# F20_NoMCU_PDM_V1.net
KiCad netlist of a schematic drawn in EAGLE
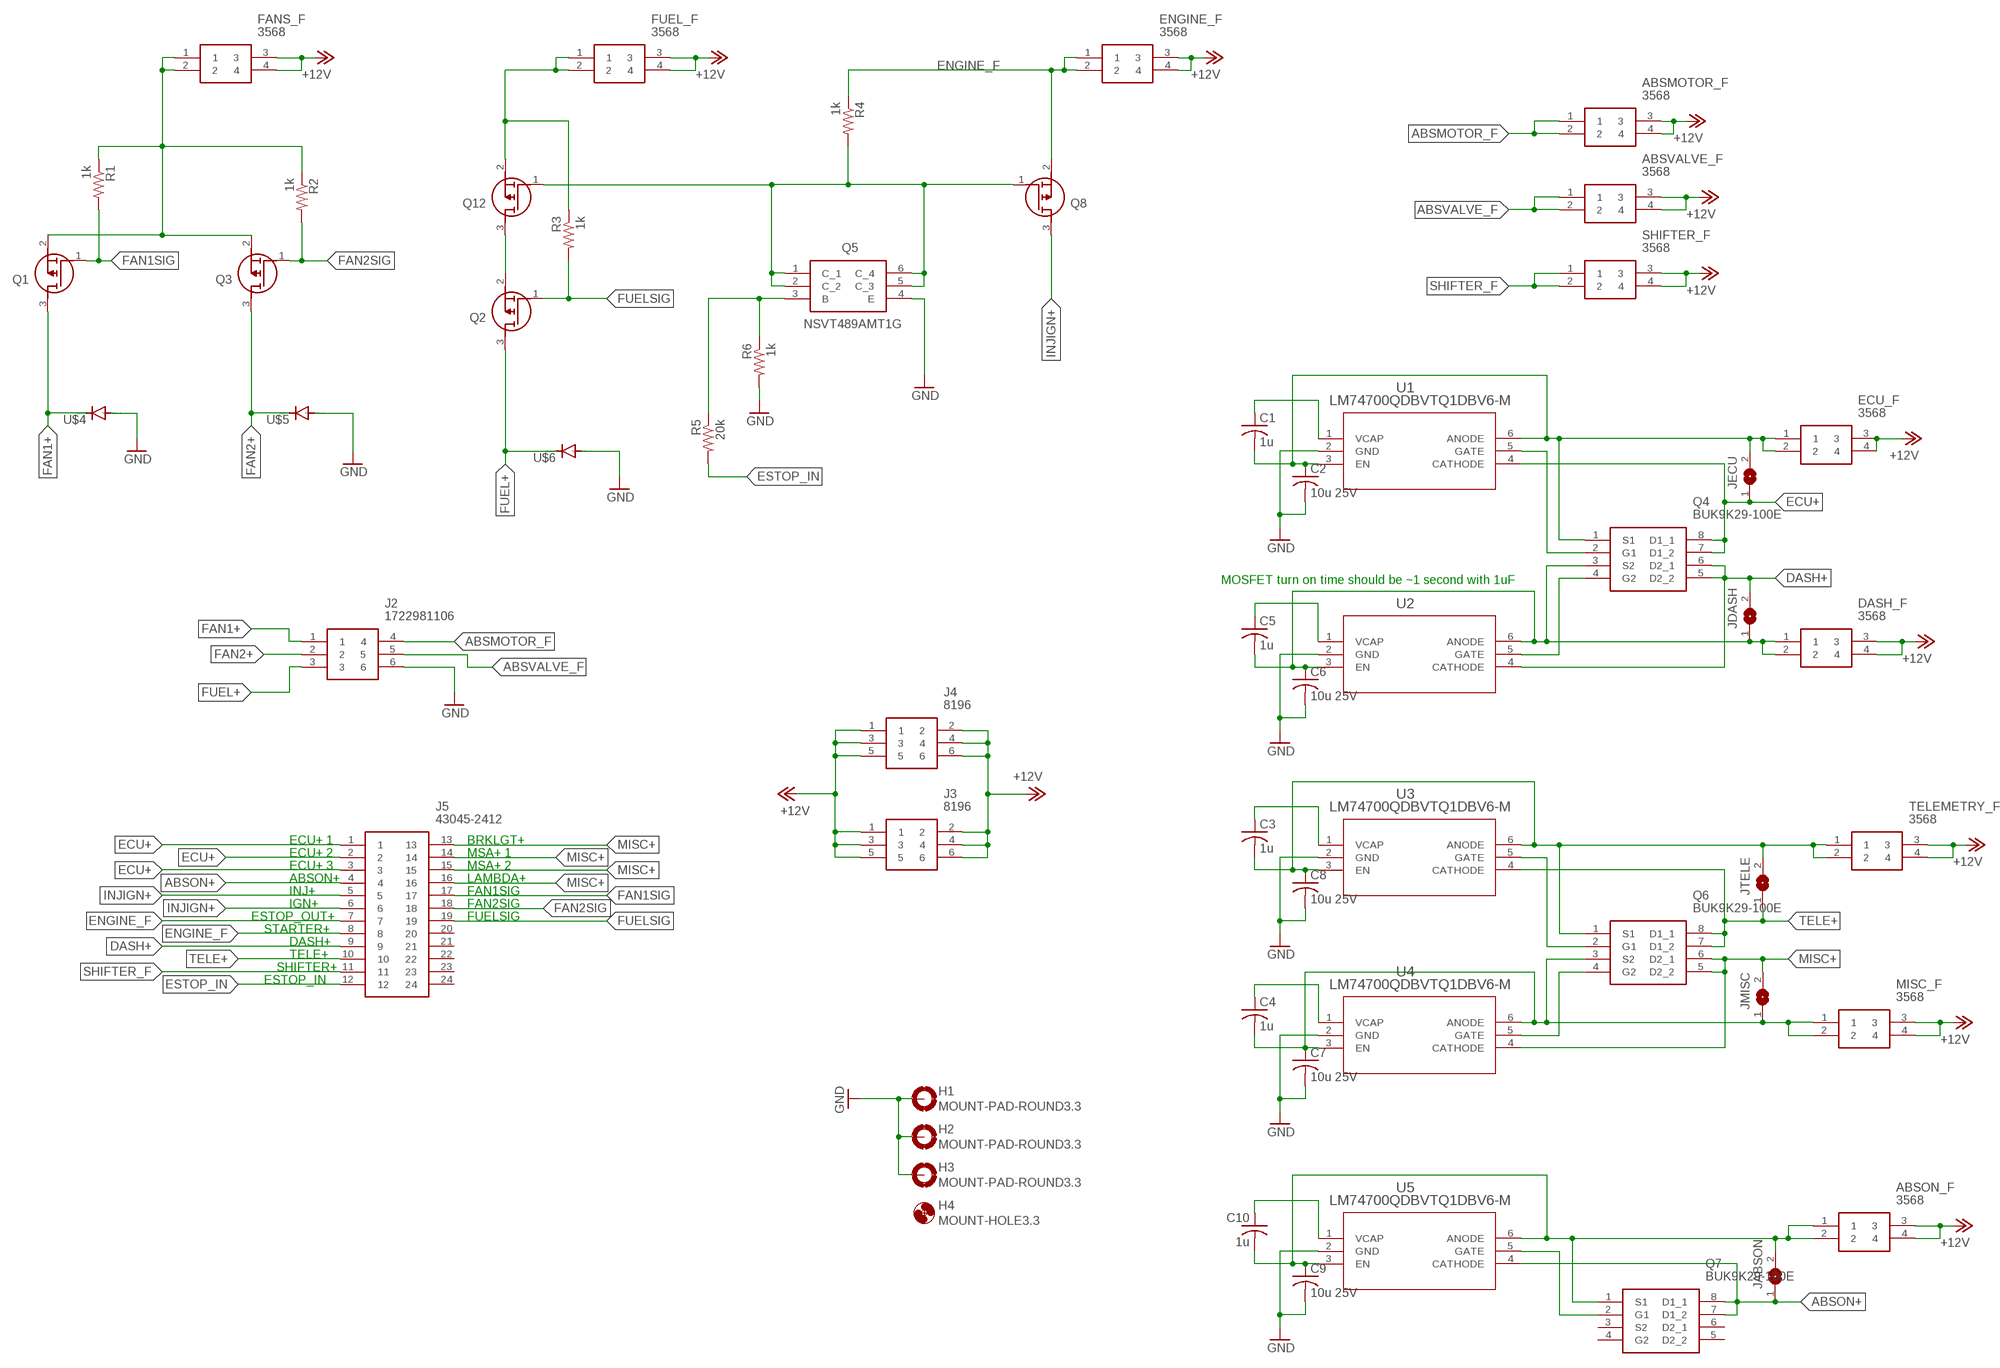
[diagram p0: schematic, sheet 1]

(export (version "E")
  (design (tool "Eeschema 10.0.6"))
  (components
    (comp (ref "ABSMOTOR_F")
      (value "3568")
      (footprint "eagle-import:3568")
      (fields (field (name "MOUSER_PART_NUMBER") "534-3568"))
      (libsource (lib "eagle-import") (part "3568"))
    )
    (comp (ref "ABSON_F")
      (value "3568")
      (footprint "eagle-import:3568")
      (fields (field (name "MOUSER_PART_NUMBER") "534-3568"))
      (libsource (lib "eagle-import") (part "3568"))
    )
    (comp (ref "ABSVALVE_F")
      (value "3568")
      (footprint "eagle-import:3568")
      (fields (field (name "MOUSER_PART_NUMBER") "534-3568"))
      (libsource (lib "eagle-import") (part "3568"))
    )
    (comp (ref "C1")
      (value "1u")
      (footprint "eagle-import:C0805")
      (libsource (lib "eagle-import") (part "C-USC0805"))
    )
    (comp (ref "C2")
      (value "10u 25V")
      (footprint "eagle-import:C0805")
      (libsource (lib "eagle-import") (part "C-USC0805"))
    )
    (comp (ref "C3")
      (value "1u")
      (footprint "eagle-import:C0805")
      (libsource (lib "eagle-import") (part "C-USC0805"))
    )
    (comp (ref "C4")
      (value "1u")
      (footprint "eagle-import:C0805")
      (libsource (lib "eagle-import") (part "C-USC0805"))
    )
    (comp (ref "C5")
      (value "1u")
      (footprint "eagle-import:C0805")
      (libsource (lib "eagle-import") (part "C-USC0805"))
    )
    (comp (ref "C6")
      (value "10u 25V")
      (footprint "eagle-import:C0805")
      (libsource (lib "eagle-import") (part "C-USC0805"))
    )
    (comp (ref "C7")
      (value "10u 25V")
      (footprint "eagle-import:C0805")
      (libsource (lib "eagle-import") (part "C-USC0805"))
    )
    (comp (ref "C8")
      (value "10u 25V")
      (footprint "eagle-import:C0805")
      (libsource (lib "eagle-import") (part "C-USC0805"))
    )
    (comp (ref "C9")
      (value "10u 25V")
      (footprint "eagle-import:C0805")
      (libsource (lib "eagle-import") (part "C-USC0805"))
    )
    (comp (ref "C10")
      (value "1u")
      (footprint "eagle-import:C0805")
      (libsource (lib "eagle-import") (part "C-USC0805"))
    )
    (comp (ref "DASH_F")
      (value "3568")
      (footprint "eagle-import:3568")
      (fields (field (name "MOUSER_PART_NUMBER") "534-3568"))
      (libsource (lib "eagle-import") (part "3568"))
    )
    (comp (ref "ECU_F")
      (value "3568")
      (footprint "eagle-import:3568")
      (fields (field (name "MOUSER_PART_NUMBER") "534-3568"))
      (libsource (lib "eagle-import") (part "3568"))
    )
    (comp (ref "ENGINE_F")
      (value "3568")
      (footprint "eagle-import:3568")
      (fields (field (name "MOUSER_PART_NUMBER") "534-3568"))
      (libsource (lib "eagle-import") (part "3568"))
    )
    (comp (ref "FANS_F")
      (value "3568")
      (footprint "eagle-import:3568")
      (fields (field (name "MOUSER_PART_NUMBER") "534-3568"))
      (libsource (lib "eagle-import") (part "3568"))
    )
    (comp (ref "FUEL_F")
      (value "3568")
      (footprint "eagle-import:3568")
      (fields (field (name "MOUSER_PART_NUMBER") "534-3568"))
      (libsource (lib "eagle-import") (part "3568"))
    )
    (comp (ref "H1")
      (value "MOUNT-PAD-ROUND3.3")
      (footprint "eagle-import:3,3-PAD")
      (libsource (lib "eagle-import") (part "MOUNT-PAD-ROUND3.3"))
    )
    (comp (ref "H2")
      (value "MOUNT-PAD-ROUND3.3")
      (footprint "eagle-import:3,3-PAD")
      (libsource (lib "eagle-import") (part "MOUNT-PAD-ROUND3.3"))
    )
    (comp (ref "H3")
      (value "MOUNT-PAD-ROUND3.3")
      (footprint "eagle-import:3,3-PAD")
      (libsource (lib "eagle-import") (part "MOUNT-PAD-ROUND3.3"))
    )
    (comp (ref "H4")
      (value "MOUNT-HOLE3.3")
      (footprint "eagle-import:3,3")
      (libsource (lib "eagle-import") (part "MOUNT-HOLE3.3"))
    )
    (comp (ref "J2")
      (value "1722981106")
      (footprint "eagle-import:1722981106")
      (libsource (lib "eagle-import") (part "1722981106"))
    )
    (comp (ref "J3")
      (value "8196")
      (footprint "eagle-import:8196")
      (fields (field (name "MOUSER_PART_NUMBER") "534-8196"))
      (libsource (lib "eagle-import") (part "8196"))
    )
    (comp (ref "J4")
      (value "8196")
      (footprint "eagle-import:8196")
      (fields (field (name "MOUSER_PART_NUMBER") "534-8196"))
      (libsource (lib "eagle-import") (part "8196"))
    )
    (comp (ref "J5")
      (value "43045-2412")
      (footprint "eagle-import:43045-2412")
      (fields (field (name "MOUSER_PART_NUMBER") "538-43045-2412"))
      (libsource (lib "eagle-import") (part "43045-2412"))
    )
    (comp (ref "JABSON")
      (value "SJ")
      (footprint "eagle-import:SJ")
      (libsource (lib "eagle-import") (part "SJ"))
    )
    (comp (ref "JDASH")
      (value "SJ")
      (footprint "eagle-import:SJ")
      (libsource (lib "eagle-import") (part "SJ"))
    )
    (comp (ref "JECU")
      (value "SJ")
      (footprint "eagle-import:SJ")
      (libsource (lib "eagle-import") (part "SJ"))
    )
    (comp (ref "JMISC")
      (value "SJ")
      (footprint "eagle-import:SJ")
      (libsource (lib "eagle-import") (part "SJ"))
    )
    (comp (ref "JTELE")
      (value "SJ")
      (footprint "eagle-import:SJ")
      (libsource (lib "eagle-import") (part "SJ"))
    )
    (comp (ref "MISC_F")
      (value "3568")
      (footprint "eagle-import:3568")
      (fields (field (name "MOUSER_PART_NUMBER") "534-3568"))
      (libsource (lib "eagle-import") (part "3568"))
    )
    (comp (ref "Q1")
      (value "IPB120P04P4L03ATMA1")
      (footprint "eagle-import:PG-TO263-3-2_1")
      (fields (field (name "MOUSER_PART_NUMBER") "726-IPB120P04P4L03AT"))
      (libsource (lib "eagle-import") (part "IPB120P04P4L03ATMA1"))
    )
    (comp (ref "Q2")
      (value "IPB120P04P4L03ATMA1")
      (footprint "eagle-import:PG-TO263-3-2_1")
      (fields (field (name "MOUSER_PART_NUMBER") "726-IPB120P04P4L03AT"))
      (libsource (lib "eagle-import") (part "IPB120P04P4L03ATMA1"))
    )
    (comp (ref "Q3")
      (value "IPB120P04P4L03ATMA1")
      (footprint "eagle-import:PG-TO263-3-2_1")
      (fields (field (name "MOUSER_PART_NUMBER") "726-IPB120P04P4L03AT"))
      (libsource (lib "eagle-import") (part "IPB120P04P4L03ATMA1"))
    )
    (comp (ref "Q4")
      (value "BUK9K29-100E")
      (footprint "eagle-import:SOIC127P605X105-8N")
      (fields
        (field (name "MANUFACTURER_PART_NUMBER") "PHPT610030NPKX")
        (field (name "MOUSER2_PART_NUMBER") "771-PHPT610030NPKX")
      )
      (libsource (lib "eagle-import") (part "BUK9K29-100E"))
    )
    (comp (ref "Q5")
      (value "NSVT489AMT1G")
      (footprint "eagle-import:SOT95P275X110-6N")
      (fields (field (name "MOUSER_PART_NUMBER") "863-NSVT489AMT1G"))
      (libsource (lib "eagle-import") (part "NSVT489AMT1G"))
    )
    (comp (ref "Q6")
      (value "BUK9K29-100E")
      (footprint "eagle-import:SOIC127P605X105-8N")
      (fields
        (field (name "MANUFACTURER_PART_NUMBER") "PHPT610030NPKX")
        (field (name "MOUSER2_PART_NUMBER") "771-PHPT610030NPKX")
      )
      (libsource (lib "eagle-import") (part "BUK9K29-100E"))
    )
    (comp (ref "Q7")
      (value "BUK9K29-100E")
      (footprint "eagle-import:SOIC127P605X105-8N")
      (fields
        (field (name "MANUFACTURER_PART_NUMBER") "PHPT610030NPKX")
        (field (name "MOUSER2_PART_NUMBER") "771-PHPT610030NPKX")
      )
      (libsource (lib "eagle-import") (part "BUK9K29-100E"))
    )
    (comp (ref "Q8")
      (value "IPB120P04P4L03ATMA1")
      (footprint "eagle-import:PG-TO263-3-2_1")
      (fields (field (name "MOUSER_PART_NUMBER") "726-IPB120P04P4L03AT"))
      (libsource (lib "eagle-import") (part "IPB120P04P4L03ATMA1"))
    )
    (comp (ref "Q12")
      (value "IPB120P04P4L03ATMA1")
      (footprint "eagle-import:PG-TO263-3-2_1")
      (fields (field (name "MOUSER_PART_NUMBER") "726-IPB120P04P4L03AT"))
      (libsource (lib "eagle-import") (part "IPB120P04P4L03ATMA1"))
    )
    (comp (ref "R1")
      (value "1k")
      (footprint "eagle-import:R0805")
      (libsource (lib "eagle-import") (part "R-US_R0805"))
    )
    (comp (ref "R2")
      (value "1k")
      (footprint "eagle-import:R0805")
      (libsource (lib "eagle-import") (part "R-US_R0805"))
    )
    (comp (ref "R3")
      (value "1k")
      (footprint "eagle-import:R0805")
      (libsource (lib "eagle-import") (part "R-US_R0805"))
    )
    (comp (ref "R4")
      (value "1k")
      (footprint "eagle-import:R0805")
      (libsource (lib "eagle-import") (part "R-US_R0805"))
    )
    (comp (ref "R5")
      (value "20k")
      (footprint "eagle-import:R0805")
      (libsource (lib "eagle-import") (part "R-US_R0805"))
    )
    (comp (ref "R6")
      (value "1k")
      (footprint "eagle-import:R0805")
      (libsource (lib "eagle-import") (part "R-US_R0805"))
    )
    (comp (ref "SHIFTER_F")
      (value "3568")
      (footprint "eagle-import:3568")
      (fields (field (name "MOUSER_PART_NUMBER") "534-3568"))
      (libsource (lib "eagle-import") (part "3568"))
    )
    (comp (ref "TELEMETRY_F")
      (value "3568")
      (footprint "eagle-import:3568")
      (fields (field (name "MOUSER_PART_NUMBER") "534-3568"))
      (libsource (lib "eagle-import") (part "3568"))
    )
    (comp (ref "U$4")
      (value "S10AL-TP")
      (footprint "eagle-import:DIOM7959X265N")
      (libsource (lib "eagle-import") (part "S10AL-TP"))
    )
    (comp (ref "U$5")
      (value "S10AL-TP")
      (footprint "eagle-import:DIOM7959X265N")
      (libsource (lib "eagle-import") (part "S10AL-TP"))
    )
    (comp (ref "U$6")
      (value "S10AL-TP")
      (footprint "eagle-import:DIOM7959X265N")
      (libsource (lib "eagle-import") (part "S10AL-TP"))
    )
    (comp (ref "U1")
      (value "LM74700QDBVTQ1DBV6-M")
      (footprint "eagle-import:DBV6-M")
      (fields
        (field (name "MANUFACTURER_PART_NUMBER") "LM74700QDBVTQ1")
        (field (name "COPYRIGHT") "Copyright (C) 2016 Accelerated Designs. All rights reserved")
      )
      (libsource (lib "eagle-import") (part "LM74700QDBVTQ1DBV6-M"))
    )
    (comp (ref "U2")
      (value "LM74700QDBVTQ1DBV6-M")
      (footprint "eagle-import:DBV6-M")
      (fields
        (field (name "MANUFACTURER_PART_NUMBER") "LM74700QDBVTQ1")
        (field (name "COPYRIGHT") "Copyright (C) 2016 Accelerated Designs. All rights reserved")
      )
      (libsource (lib "eagle-import") (part "LM74700QDBVTQ1DBV6-M"))
    )
    (comp (ref "U3")
      (value "LM74700QDBVTQ1DBV6-M")
      (footprint "eagle-import:DBV6-M")
      (fields
        (field (name "MANUFACTURER_PART_NUMBER") "LM74700QDBVTQ1")
        (field (name "COPYRIGHT") "Copyright (C) 2016 Accelerated Designs. All rights reserved")
      )
      (libsource (lib "eagle-import") (part "LM74700QDBVTQ1DBV6-M"))
    )
    (comp (ref "U4")
      (value "LM74700QDBVTQ1DBV6-M")
      (footprint "eagle-import:DBV6-M")
      (fields
        (field (name "MANUFACTURER_PART_NUMBER") "LM74700QDBVTQ1")
        (field (name "COPYRIGHT") "Copyright (C) 2016 Accelerated Designs. All rights reserved")
      )
      (libsource (lib "eagle-import") (part "LM74700QDBVTQ1DBV6-M"))
    )
    (comp (ref "U5")
      (value "LM74700QDBVTQ1DBV6-M")
      (footprint "eagle-import:DBV6-M")
      (fields
        (field (name "MANUFACTURER_PART_NUMBER") "LM74700QDBVTQ1")
        (field (name "COPYRIGHT") "Copyright (C) 2016 Accelerated Designs. All rights reserved")
      )
      (libsource (lib "eagle-import") (part "LM74700QDBVTQ1DBV6-M"))
    )
  )
  (nets
    (net (code "1") (name "+12V") (class "Default")
      (node (ref "ABSMOTOR_F") (pin "3") (pinfunction "3_3") (pintype "bidirectional"))
      (node (ref "ABSMOTOR_F") (pin "4") (pinfunction "4_4") (pintype "bidirectional"))
      (node (ref "ABSON_F") (pin "3") (pinfunction "3_3") (pintype "bidirectional"))
      (node (ref "ABSON_F") (pin "4") (pinfunction "4_4") (pintype "bidirectional"))
      (node (ref "ABSVALVE_F") (pin "3") (pinfunction "3_3") (pintype "bidirectional"))
      (node (ref "ABSVALVE_F") (pin "4") (pinfunction "4_4") (pintype "bidirectional"))
      (node (ref "DASH_F") (pin "3") (pinfunction "3_3") (pintype "bidirectional"))
      (node (ref "DASH_F") (pin "4") (pinfunction "4_4") (pintype "bidirectional"))
      (node (ref "ECU_F") (pin "3") (pinfunction "3_3") (pintype "bidirectional"))
      (node (ref "ECU_F") (pin "4") (pinfunction "4_4") (pintype "bidirectional"))
      (node (ref "ENGINE_F") (pin "3") (pinfunction "3_3") (pintype "bidirectional"))
      (node (ref "ENGINE_F") (pin "4") (pinfunction "4_4") (pintype "bidirectional"))
      (node (ref "FANS_F") (pin "3") (pinfunction "3_3") (pintype "bidirectional"))
      (node (ref "FANS_F") (pin "4") (pinfunction "4_4") (pintype "bidirectional"))
      (node (ref "FUEL_F") (pin "3") (pinfunction "3_3") (pintype "bidirectional"))
      (node (ref "FUEL_F") (pin "4") (pinfunction "4_4") (pintype "bidirectional"))
      (node (ref "J3") (pin "1") (pinfunction "1_1") (pintype "bidirectional"))
      (node (ref "J3") (pin "2") (pinfunction "2_2") (pintype "bidirectional"))
      (node (ref "J3") (pin "3") (pinfunction "3_3") (pintype "bidirectional"))
      (node (ref "J3") (pin "4") (pinfunction "4_4") (pintype "bidirectional"))
      (node (ref "J3") (pin "5") (pinfunction "5_5") (pintype "bidirectional"))
      (node (ref "J3") (pin "6") (pinfunction "6_6") (pintype "bidirectional"))
      (node (ref "J4") (pin "1") (pinfunction "1_1") (pintype "bidirectional"))
      (node (ref "J4") (pin "2") (pinfunction "2_2") (pintype "bidirectional"))
      (node (ref "J4") (pin "3") (pinfunction "3_3") (pintype "bidirectional"))
      (node (ref "J4") (pin "4") (pinfunction "4_4") (pintype "bidirectional"))
      (node (ref "J4") (pin "5") (pinfunction "5_5") (pintype "bidirectional"))
      (node (ref "J4") (pin "6") (pinfunction "6_6") (pintype "bidirectional"))
      (node (ref "MISC_F") (pin "3") (pinfunction "3_3") (pintype "bidirectional"))
      (node (ref "MISC_F") (pin "4") (pinfunction "4_4") (pintype "bidirectional"))
      (node (ref "SHIFTER_F") (pin "3") (pinfunction "3_3") (pintype "bidirectional"))
      (node (ref "SHIFTER_F") (pin "4") (pinfunction "4_4") (pintype "bidirectional"))
      (node (ref "TELEMETRY_F") (pin "3") (pinfunction "3_3") (pintype "bidirectional"))
      (node (ref "TELEMETRY_F") (pin "4") (pinfunction "4_4") (pintype "bidirectional"))
    )
    (net (code "2") (name "ABSMOTOR_F") (class "Default")
      (node (ref "ABSMOTOR_F") (pin "1") (pinfunction "1_1") (pintype "bidirectional"))
      (node (ref "ABSMOTOR_F") (pin "2") (pinfunction "2_2") (pintype "bidirectional"))
      (node (ref "J2") (pin "4") (pinfunction "4_4") (pintype "bidirectional"))
    )
    (net (code "3") (name "ABSON+") (class "Default")
      (node (ref "J5") (pin "4") (pinfunction "4_4") (pintype "bidirectional"))
      (node (ref "JABSON") (pin "1") (pinfunction "1_1") (pintype "passive"))
      (node (ref "Q7") (pin "7") (pinfunction "D1_2_7") (pintype "bidirectional"))
      (node (ref "Q7") (pin "8") (pinfunction "D1_1_8") (pintype "bidirectional"))
      (node (ref "U5") (pin "4") (pinfunction "CATHODE_4") (pintype "input"))
    )
    (net (code "4") (name "ABSVALVE_F") (class "Default")
      (node (ref "ABSVALVE_F") (pin "1") (pinfunction "1_1") (pintype "bidirectional"))
      (node (ref "ABSVALVE_F") (pin "2") (pinfunction "2_2") (pintype "bidirectional"))
      (node (ref "J2") (pin "5") (pinfunction "5_5") (pintype "bidirectional"))
    )
    (net (code "5") (name "DASH+") (class "Default")
      (node (ref "J5") (pin "9") (pinfunction "9_9") (pintype "bidirectional"))
      (node (ref "JDASH") (pin "2") (pinfunction "2_2") (pintype "passive"))
      (node (ref "Q4") (pin "5") (pinfunction "D2_2_5") (pintype "bidirectional"))
      (node (ref "Q4") (pin "6") (pinfunction "D2_1_6") (pintype "bidirectional"))
      (node (ref "U2") (pin "4") (pinfunction "CATHODE_4") (pintype "input"))
    )
    (net (code "6") (name "ECU+") (class "Default")
      (node (ref "J5") (pin "1") (pinfunction "1_1") (pintype "bidirectional"))
      (node (ref "J5") (pin "2") (pinfunction "2_2") (pintype "bidirectional"))
      (node (ref "J5") (pin "3") (pinfunction "3_3") (pintype "bidirectional"))
      (node (ref "JECU") (pin "1") (pinfunction "1_1") (pintype "passive"))
      (node (ref "Q4") (pin "7") (pinfunction "D1_2_7") (pintype "bidirectional"))
      (node (ref "Q4") (pin "8") (pinfunction "D1_1_8") (pintype "bidirectional"))
      (node (ref "U1") (pin "4") (pinfunction "CATHODE_4") (pintype "input"))
    )
    (net (code "7") (name "ENGINE_F") (class "Default")
      (node (ref "ENGINE_F") (pin "1") (pinfunction "1_1") (pintype "bidirectional"))
      (node (ref "ENGINE_F") (pin "2") (pinfunction "2_2") (pintype "bidirectional"))
      (node (ref "J5") (pin "7") (pinfunction "7_7") (pintype "bidirectional"))
      (node (ref "J5") (pin "8") (pinfunction "8_8") (pintype "bidirectional"))
      (node (ref "Q8") (pin "2") (pinfunction "S_2") (pintype "bidirectional"))
      (node (ref "R4") (pin "1") (pinfunction "1_1") (pintype "passive"))
    )
    (net (code "8") (name "ESTOP_IN") (class "Default")
      (node (ref "J5") (pin "12") (pinfunction "12_12") (pintype "bidirectional"))
      (node (ref "R5") (pin "2") (pinfunction "2_2") (pintype "passive"))
    )
    (net (code "9") (name "FAN1+") (class "Default")
      (node (ref "J2") (pin "1") (pinfunction "1_1") (pintype "bidirectional"))
      (node (ref "Q1") (pin "3") (pinfunction "D_3") (pintype "bidirectional"))
      (node (ref "U$4") (pin "C") (pinfunction "C_C") (pintype "passive"))
    )
    (net (code "10") (name "FAN1SIG") (class "Default")
      (node (ref "J5") (pin "17") (pinfunction "17_17") (pintype "bidirectional"))
      (node (ref "Q1") (pin "1") (pinfunction "G_1") (pintype "bidirectional"))
      (node (ref "R1") (pin "2") (pinfunction "2_2") (pintype "passive"))
    )
    (net (code "11") (name "FAN2+") (class "Default")
      (node (ref "J2") (pin "2") (pinfunction "2_2") (pintype "bidirectional"))
      (node (ref "Q3") (pin "3") (pinfunction "D_3") (pintype "bidirectional"))
      (node (ref "U$5") (pin "C") (pinfunction "C_C") (pintype "passive"))
    )
    (net (code "12") (name "FAN2SIG") (class "Default")
      (node (ref "J5") (pin "18") (pinfunction "18_18") (pintype "bidirectional"))
      (node (ref "Q3") (pin "1") (pinfunction "G_1") (pintype "bidirectional"))
      (node (ref "R2") (pin "2") (pinfunction "2_2") (pintype "passive"))
    )
    (net (code "13") (name "FUEL+") (class "Default")
      (node (ref "J2") (pin "3") (pinfunction "3_3") (pintype "bidirectional"))
      (node (ref "Q2") (pin "3") (pinfunction "D_3") (pintype "bidirectional"))
      (node (ref "U$6") (pin "C") (pinfunction "C_C") (pintype "passive"))
    )
    (net (code "14") (name "FUELSIG") (class "Default")
      (node (ref "J5") (pin "19") (pinfunction "19_19") (pintype "bidirectional"))
      (node (ref "Q2") (pin "1") (pinfunction "G_1") (pintype "bidirectional"))
      (node (ref "R3") (pin "2") (pinfunction "2_2") (pintype "passive"))
    )
    (net (code "15") (name "GND") (class "Default")
      (node (ref "C2") (pin "2") (pinfunction "2_2") (pintype "passive"))
      (node (ref "C6") (pin "2") (pinfunction "2_2") (pintype "passive"))
      (node (ref "C7") (pin "2") (pinfunction "2_2") (pintype "passive"))
      (node (ref "C8") (pin "2") (pinfunction "2_2") (pintype "passive"))
      (node (ref "C9") (pin "2") (pinfunction "2_2") (pintype "passive"))
      (node (ref "H1") (pin "B3,3") (pinfunction "MOUNT_B3,3") (pintype "passive"))
      (node (ref "H2") (pin "B3,3") (pinfunction "MOUNT_B3,3") (pintype "passive"))
      (node (ref "H3") (pin "B3,3") (pinfunction "MOUNT_B3,3") (pintype "passive"))
      (node (ref "J2") (pin "6") (pinfunction "6_6") (pintype "bidirectional"))
      (node (ref "Q5") (pin "4") (pinfunction "E_4") (pintype "bidirectional"))
      (node (ref "R6") (pin "2") (pinfunction "2_2") (pintype "passive"))
      (node (ref "U$4") (pin "A") (pinfunction "A_A") (pintype "passive"))
      (node (ref "U$5") (pin "A") (pinfunction "A_A") (pintype "passive"))
      (node (ref "U$6") (pin "A") (pinfunction "A_A") (pintype "passive"))
      (node (ref "U1") (pin "2") (pinfunction "GND_2") (pintype "power_in"))
      (node (ref "U2") (pin "2") (pinfunction "GND_2") (pintype "power_in"))
      (node (ref "U3") (pin "2") (pinfunction "GND_2") (pintype "power_in"))
      (node (ref "U4") (pin "2") (pinfunction "GND_2") (pintype "power_in"))
      (node (ref "U5") (pin "2") (pinfunction "GND_2") (pintype "power_in"))
    )
    (net (code "16") (name "INJIGN+") (class "Default")
      (node (ref "J5") (pin "5") (pinfunction "5_5") (pintype "bidirectional"))
      (node (ref "J5") (pin "6") (pinfunction "6_6") (pintype "bidirectional"))
      (node (ref "Q8") (pin "3") (pinfunction "D_3") (pintype "bidirectional"))
    )
    (net (code "17") (name "MISC+") (class "Default")
      (node (ref "J5") (pin "13") (pinfunction "13_13") (pintype "bidirectional"))
      (node (ref "J5") (pin "14") (pinfunction "14_14") (pintype "bidirectional"))
      (node (ref "J5") (pin "15") (pinfunction "15_15") (pintype "bidirectional"))
      (node (ref "J5") (pin "16") (pinfunction "16_16") (pintype "bidirectional"))
      (node (ref "JMISC") (pin "2") (pinfunction "2_2") (pintype "passive"))
      (node (ref "Q6") (pin "5") (pinfunction "D2_2_5") (pintype "bidirectional"))
      (node (ref "Q6") (pin "6") (pinfunction "D2_1_6") (pintype "bidirectional"))
      (node (ref "U4") (pin "4") (pinfunction "CATHODE_4") (pintype "input"))
    )
    (net (code "18") (name "Net-(Q1-S)") (class "Default")
      (node (ref "FANS_F") (pin "1") (pinfunction "1_1") (pintype "bidirectional"))
      (node (ref "FANS_F") (pin "2") (pinfunction "2_2") (pintype "bidirectional"))
      (node (ref "Q1") (pin "2") (pinfunction "S_2") (pintype "bidirectional"))
      (node (ref "Q3") (pin "2") (pinfunction "S_2") (pintype "bidirectional"))
      (node (ref "R1") (pin "1") (pinfunction "1_1") (pintype "passive"))
      (node (ref "R2") (pin "1") (pinfunction "1_1") (pintype "passive"))
    )
    (net (code "19") (name "Net-(Q4-G1)") (class "Default")
      (node (ref "Q4") (pin "2") (pinfunction "G1_2") (pintype "bidirectional"))
      (node (ref "U1") (pin "5") (pinfunction "GATE_5") (pintype "output"))
    )
    (net (code "20") (name "Net-(Q4-G2)") (class "Default")
      (node (ref "Q4") (pin "4") (pinfunction "G2_4") (pintype "bidirectional"))
      (node (ref "U2") (pin "5") (pinfunction "GATE_5") (pintype "output"))
    )
    (net (code "21") (name "Net-(Q4-S1)") (class "Default")
      (node (ref "C1") (pin "2") (pinfunction "2_2") (pintype "passive"))
      (node (ref "C2") (pin "1") (pinfunction "1_1") (pintype "passive"))
      (node (ref "ECU_F") (pin "1") (pinfunction "1_1") (pintype "bidirectional"))
      (node (ref "ECU_F") (pin "2") (pinfunction "2_2") (pintype "bidirectional"))
      (node (ref "JECU") (pin "2") (pinfunction "2_2") (pintype "passive"))
      (node (ref "Q4") (pin "1") (pinfunction "S1_1") (pintype "bidirectional"))
      (node (ref "U1") (pin "3") (pinfunction "EN_3") (pintype "input"))
      (node (ref "U1") (pin "6") (pinfunction "ANODE_6") (pintype "input"))
    )
    (net (code "22") (name "Net-(Q4-S2)") (class "Default")
      (node (ref "C5") (pin "2") (pinfunction "2_2") (pintype "passive"))
      (node (ref "C6") (pin "1") (pinfunction "1_1") (pintype "passive"))
      (node (ref "DASH_F") (pin "1") (pinfunction "1_1") (pintype "bidirectional"))
      (node (ref "DASH_F") (pin "2") (pinfunction "2_2") (pintype "bidirectional"))
      (node (ref "JDASH") (pin "1") (pinfunction "1_1") (pintype "passive"))
      (node (ref "Q4") (pin "3") (pinfunction "S2_3") (pintype "bidirectional"))
      (node (ref "U2") (pin "3") (pinfunction "EN_3") (pintype "input"))
      (node (ref "U2") (pin "6") (pinfunction "ANODE_6") (pintype "input"))
    )
    (net (code "23") (name "Net-(Q5-B)") (class "Default")
      (node (ref "Q5") (pin "3") (pinfunction "B_3") (pintype "bidirectional"))
      (node (ref "R5") (pin "1") (pinfunction "1_1") (pintype "passive"))
      (node (ref "R6") (pin "1") (pinfunction "1_1") (pintype "passive"))
    )
    (net (code "24") (name "Net-(Q6-G1)") (class "Default")
      (node (ref "Q6") (pin "2") (pinfunction "G1_2") (pintype "bidirectional"))
      (node (ref "U3") (pin "5") (pinfunction "GATE_5") (pintype "output"))
    )
    (net (code "25") (name "Net-(Q6-G2)") (class "Default")
      (node (ref "Q6") (pin "4") (pinfunction "G2_4") (pintype "bidirectional"))
      (node (ref "U4") (pin "5") (pinfunction "GATE_5") (pintype "output"))
    )
    (net (code "26") (name "Net-(Q6-S1)") (class "Default")
      (node (ref "C3") (pin "2") (pinfunction "2_2") (pintype "passive"))
      (node (ref "C8") (pin "1") (pinfunction "1_1") (pintype "passive"))
      (node (ref "JTELE") (pin "2") (pinfunction "2_2") (pintype "passive"))
      (node (ref "Q6") (pin "1") (pinfunction "S1_1") (pintype "bidirectional"))
      (node (ref "TELEMETRY_F") (pin "1") (pinfunction "1_1") (pintype "bidirectional"))
      (node (ref "TELEMETRY_F") (pin "2") (pinfunction "2_2") (pintype "bidirectional"))
      (node (ref "U3") (pin "3") (pinfunction "EN_3") (pintype "input"))
      (node (ref "U3") (pin "6") (pinfunction "ANODE_6") (pintype "input"))
    )
    (net (code "27") (name "Net-(Q6-S2)") (class "Default")
      (node (ref "C4") (pin "2") (pinfunction "2_2") (pintype "passive"))
      (node (ref "C7") (pin "1") (pinfunction "1_1") (pintype "passive"))
      (node (ref "JMISC") (pin "1") (pinfunction "1_1") (pintype "passive"))
      (node (ref "MISC_F") (pin "1") (pinfunction "1_1") (pintype "bidirectional"))
      (node (ref "MISC_F") (pin "2") (pinfunction "2_2") (pintype "bidirectional"))
      (node (ref "Q6") (pin "3") (pinfunction "S2_3") (pintype "bidirectional"))
      (node (ref "U4") (pin "3") (pinfunction "EN_3") (pintype "input"))
      (node (ref "U4") (pin "6") (pinfunction "ANODE_6") (pintype "input"))
    )
    (net (code "28") (name "Net-(Q7-G1)") (class "Default")
      (node (ref "Q7") (pin "2") (pinfunction "G1_2") (pintype "bidirectional"))
      (node (ref "U5") (pin "5") (pinfunction "GATE_5") (pintype "output"))
    )
    (net (code "29") (name "Net-(Q7-S1)") (class "Default")
      (node (ref "ABSON_F") (pin "1") (pinfunction "1_1") (pintype "bidirectional"))
      (node (ref "ABSON_F") (pin "2") (pinfunction "2_2") (pintype "bidirectional"))
      (node (ref "C10") (pin "2") (pinfunction "2_2") (pintype "passive"))
      (node (ref "C9") (pin "1") (pinfunction "1_1") (pintype "passive"))
      (node (ref "JABSON") (pin "2") (pinfunction "2_2") (pintype "passive"))
      (node (ref "Q7") (pin "1") (pinfunction "S1_1") (pintype "bidirectional"))
      (node (ref "U5") (pin "3") (pinfunction "EN_3") (pintype "input"))
      (node (ref "U5") (pin "6") (pinfunction "ANODE_6") (pintype "input"))
    )
    (net (code "30") (name "Net-(Q12-D)") (class "Default")
      (node (ref "Q12") (pin "3") (pinfunction "D_3") (pintype "bidirectional"))
      (node (ref "Q2") (pin "2") (pinfunction "S_2") (pintype "bidirectional"))
    )
    (net (code "31") (name "Net-(Q12-G)") (class "Default")
      (node (ref "Q12") (pin "1") (pinfunction "G_1") (pintype "bidirectional"))
      (node (ref "Q5") (pin "1") (pinfunction "C_1_1") (pintype "bidirectional"))
      (node (ref "Q5") (pin "2") (pinfunction "C_2_2") (pintype "bidirectional"))
      (node (ref "Q5") (pin "5") (pinfunction "C_3_5") (pintype "bidirectional"))
      (node (ref "Q5") (pin "6") (pinfunction "C_4_6") (pintype "bidirectional"))
      (node (ref "Q8") (pin "1") (pinfunction "G_1") (pintype "bidirectional"))
      (node (ref "R4") (pin "2") (pinfunction "2_2") (pintype "passive"))
    )
    (net (code "32") (name "Net-(Q12-S)") (class "Default")
      (node (ref "FUEL_F") (pin "1") (pinfunction "1_1") (pintype "bidirectional"))
      (node (ref "FUEL_F") (pin "2") (pinfunction "2_2") (pintype "bidirectional"))
      (node (ref "Q12") (pin "2") (pinfunction "S_2") (pintype "bidirectional"))
      (node (ref "R3") (pin "1") (pinfunction "1_1") (pintype "passive"))
    )
    (net (code "33") (name "Net-(U1-VCAP)") (class "Default")
      (node (ref "C1") (pin "1") (pinfunction "1_1") (pintype "passive"))
      (node (ref "U1") (pin "1") (pinfunction "VCAP_1") (pintype "output"))
    )
    (net (code "34") (name "Net-(U2-VCAP)") (class "Default")
      (node (ref "C5") (pin "1") (pinfunction "1_1") (pintype "passive"))
      (node (ref "U2") (pin "1") (pinfunction "VCAP_1") (pintype "output"))
    )
    (net (code "35") (name "Net-(U3-VCAP)") (class "Default")
      (node (ref "C3") (pin "1") (pinfunction "1_1") (pintype "passive"))
      (node (ref "U3") (pin "1") (pinfunction "VCAP_1") (pintype "output"))
    )
    (net (code "36") (name "Net-(U4-VCAP)") (class "Default")
      (node (ref "C4") (pin "1") (pinfunction "1_1") (pintype "passive"))
      (node (ref "U4") (pin "1") (pinfunction "VCAP_1") (pintype "output"))
    )
    (net (code "37") (name "Net-(U5-VCAP)") (class "Default")
      (node (ref "C10") (pin "1") (pinfunction "1_1") (pintype "passive"))
      (node (ref "U5") (pin "1") (pinfunction "VCAP_1") (pintype "output"))
    )
    (net (code "38") (name "SHIFTER_F") (class "Default")
      (node (ref "J5") (pin "11") (pinfunction "11_11") (pintype "bidirectional"))
      (node (ref "SHIFTER_F") (pin "1") (pinfunction "1_1") (pintype "bidirectional"))
      (node (ref "SHIFTER_F") (pin "2") (pinfunction "2_2") (pintype "bidirectional"))
    )
    (net (code "39") (name "TELE+") (class "Default")
      (node (ref "J5") (pin "10") (pinfunction "10_10") (pintype "bidirectional"))
      (node (ref "JTELE") (pin "1") (pinfunction "1_1") (pintype "passive"))
      (node (ref "Q6") (pin "7") (pinfunction "D1_2_7") (pintype "bidirectional"))
      (node (ref "Q6") (pin "8") (pinfunction "D1_1_8") (pintype "bidirectional"))
      (node (ref "U3") (pin "4") (pinfunction "CATHODE_4") (pintype "input"))
    )
    (net (code "40") (name "unconnected-(J5-Pad20)") (class "Default")
      (node (ref "J5") (pin "20") (pinfunction "20_20") (pintype "bidirectional"))
    )
    (net (code "41") (name "unconnected-(J5-Pad21)") (class "Default")
      (node (ref "J5") (pin "21") (pinfunction "21_21") (pintype "bidirectional"))
    )
    (net (code "42") (name "unconnected-(J5-Pad22)") (class "Default")
      (node (ref "J5") (pin "22") (pinfunction "22_22") (pintype "bidirectional"))
    )
    (net (code "43") (name "unconnected-(J5-Pad23)") (class "Default")
      (node (ref "J5") (pin "23") (pinfunction "23_23") (pintype "bidirectional"))
    )
    (net (code "44") (name "unconnected-(J5-Pad24)") (class "Default")
      (node (ref "J5") (pin "24") (pinfunction "24_24") (pintype "bidirectional"))
    )
    (net (code "45") (name "unconnected-(Q7-D2_1-Pad6)") (class "Default")
      (node (ref "Q7") (pin "6") (pinfunction "D2_1_6") (pintype "bidirectional"))
    )
    (net (code "46") (name "unconnected-(Q7-D2_2-Pad5)") (class "Default")
      (node (ref "Q7") (pin "5") (pinfunction "D2_2_5") (pintype "bidirectional"))
    )
    (net (code "47") (name "unconnected-(Q7-G2-Pad4)") (class "Default")
      (node (ref "Q7") (pin "4") (pinfunction "G2_4") (pintype "bidirectional"))
    )
    (net (code "48") (name "unconnected-(Q7-S2-Pad3)") (class "Default")
      (node (ref "Q7") (pin "3") (pinfunction "S2_3") (pintype "bidirectional"))
    )
  )
)
